# bmsSlave_balancing.net
KiCad netlist of a schematic drawn in Altium Designer
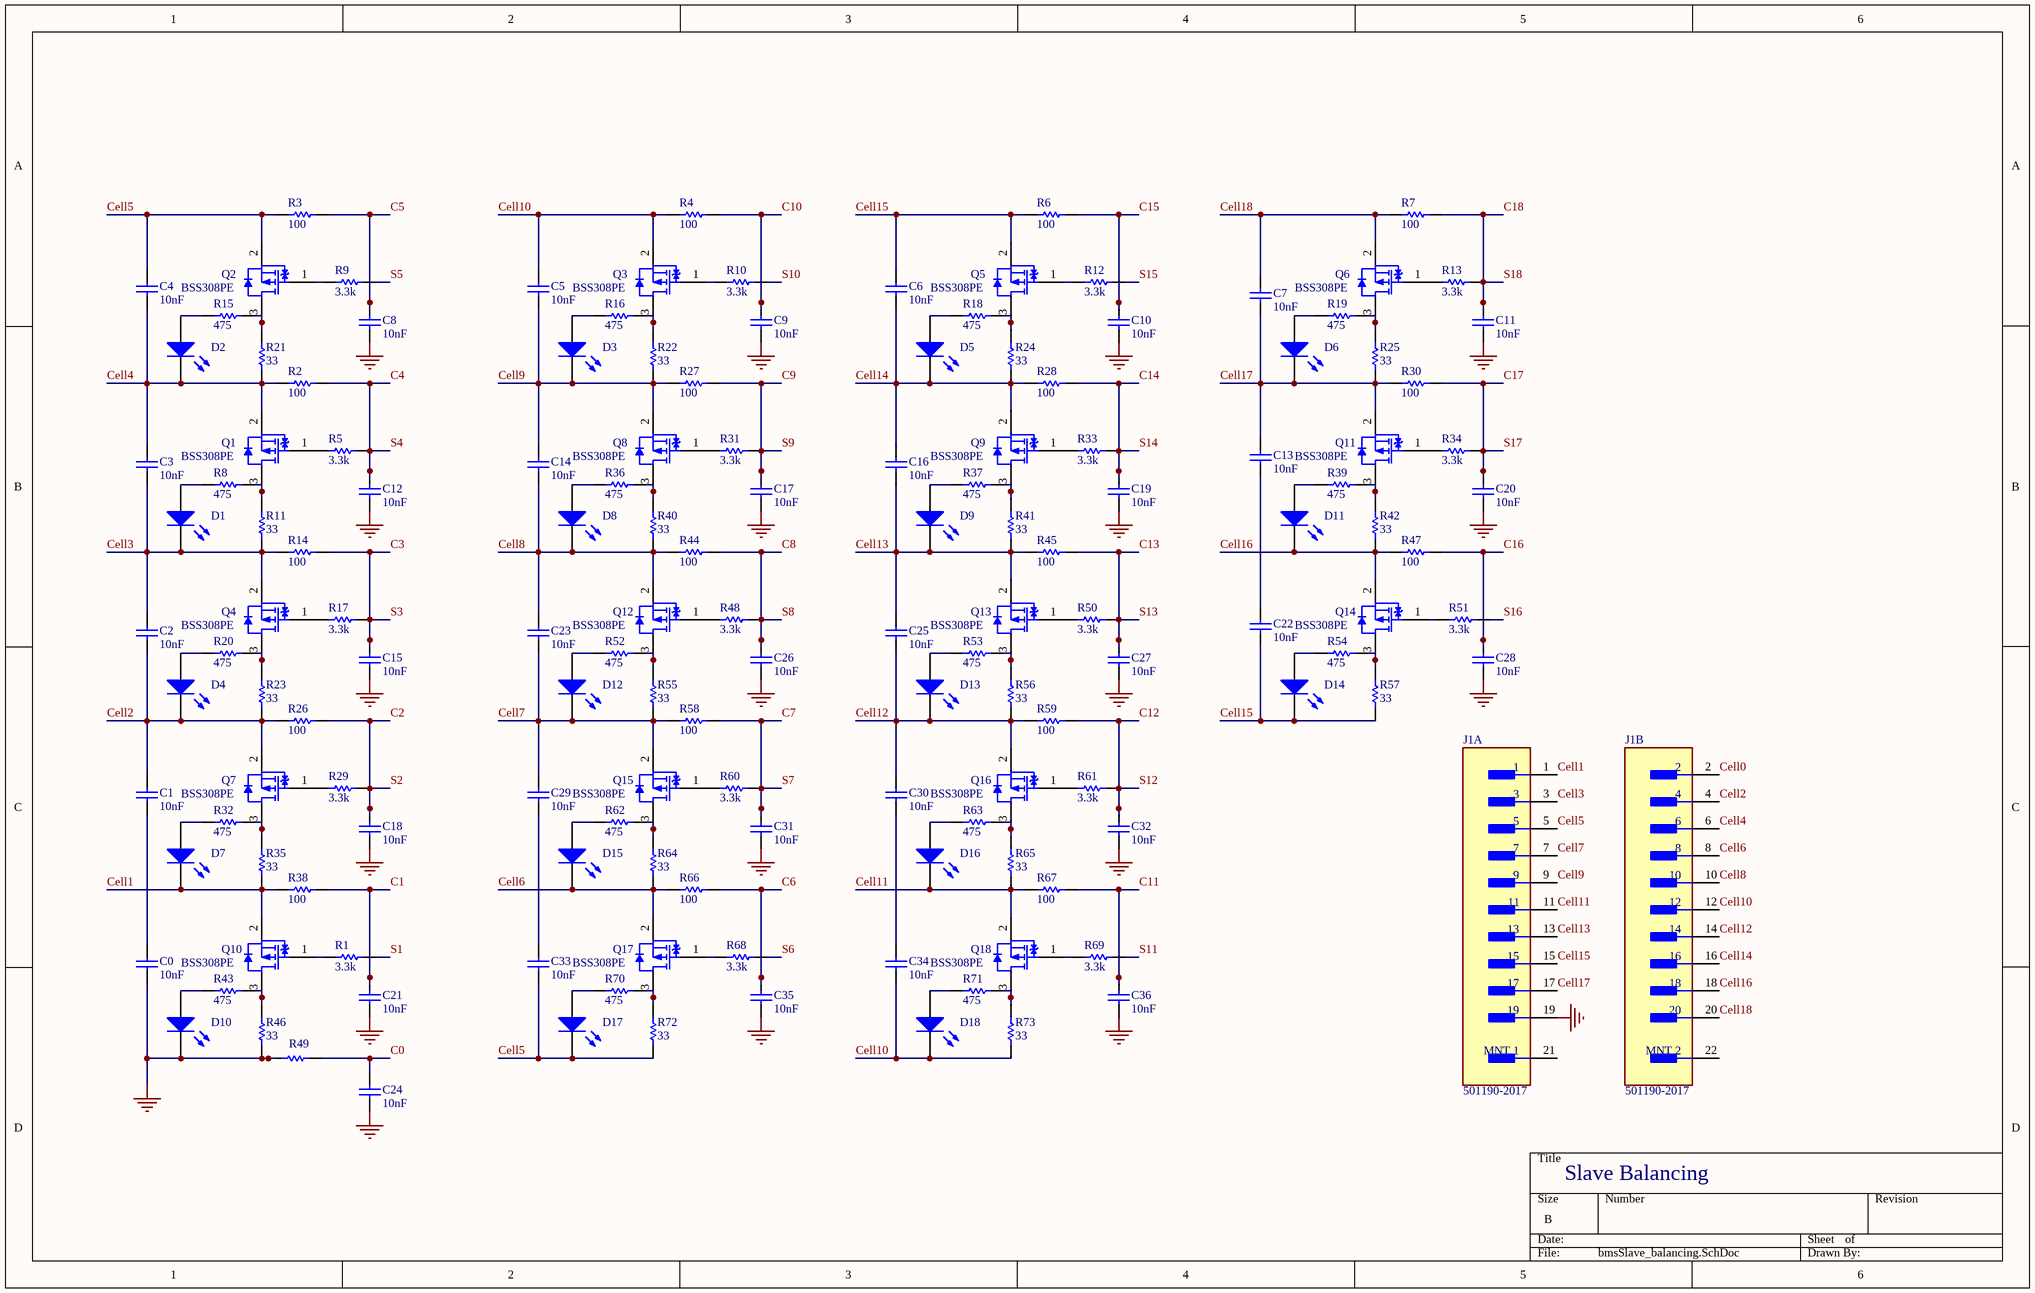
[diagram p0: bmsSlave_balancing.SchDoc]

(export (version "E")
  (design (tool "Eeschema 10.0.6"))
  (components
    (comp (ref "C0")
      (value "10nF")
      (description "Capacitor")
      (libsource (lib "Simulation Generic Components") (part "Capacitor"))
    )
    (comp (ref "C1")
      (value "10nF")
      (description "Capacitor")
      (libsource (lib "Simulation Generic Components") (part "Capacitor"))
    )
    (comp (ref "C2")
      (value "10nF")
      (description "Capacitor")
      (libsource (lib "Simulation Generic Components") (part "Capacitor"))
    )
    (comp (ref "C3")
      (value "10nF")
      (description "Capacitor")
      (libsource (lib "Simulation Generic Components") (part "Capacitor"))
    )
    (comp (ref "C4")
      (value "10nF")
      (description "Capacitor")
      (libsource (lib "Simulation Generic Components") (part "Capacitor"))
    )
    (comp (ref "C5")
      (value "10nF")
      (description "Capacitor")
      (libsource (lib "Simulation Generic Components") (part "Capacitor"))
    )
    (comp (ref "C6")
      (value "10nF")
      (description "Capacitor")
      (libsource (lib "Simulation Generic Components") (part "Capacitor"))
    )
    (comp (ref "C7")
      (value "10nF")
      (description "Capacitor")
      (libsource (lib "Simulation Generic Components") (part "Capacitor"))
    )
    (comp (ref "C8")
      (value "10nF")
      (description "Capacitor")
      (libsource (lib "Simulation Generic Components") (part "Capacitor"))
    )
    (comp (ref "C9")
      (value "10nF")
      (description "Capacitor")
      (libsource (lib "Simulation Generic Components") (part "Capacitor"))
    )
    (comp (ref "C10")
      (value "10nF")
      (description "Capacitor")
      (libsource (lib "Simulation Generic Components") (part "Capacitor"))
    )
    (comp (ref "C11")
      (value "10nF")
      (description "Capacitor")
      (libsource (lib "Simulation Generic Components") (part "Capacitor"))
    )
    (comp (ref "C12")
      (value "10nF")
      (description "Capacitor")
      (libsource (lib "Simulation Generic Components") (part "Capacitor"))
    )
    (comp (ref "C13")
      (value "10nF")
      (description "Capacitor")
      (libsource (lib "Simulation Generic Components") (part "Capacitor"))
    )
    (comp (ref "C14")
      (value "10nF")
      (description "Capacitor")
      (libsource (lib "Simulation Generic Components") (part "Capacitor"))
    )
    (comp (ref "C15")
      (value "10nF")
      (description "Capacitor")
      (libsource (lib "Simulation Generic Components") (part "Capacitor"))
    )
    (comp (ref "C16")
      (value "10nF")
      (description "Capacitor")
      (libsource (lib "Simulation Generic Components") (part "Capacitor"))
    )
    (comp (ref "C17")
      (value "10nF")
      (description "Capacitor")
      (libsource (lib "Simulation Generic Components") (part "Capacitor"))
    )
    (comp (ref "C18")
      (value "10nF")
      (description "Capacitor")
      (libsource (lib "Simulation Generic Components") (part "Capacitor"))
    )
    (comp (ref "C19")
      (value "10nF")
      (description "Capacitor")
      (libsource (lib "Simulation Generic Components") (part "Capacitor"))
    )
    (comp (ref "C20")
      (value "10nF")
      (description "Capacitor")
      (libsource (lib "Simulation Generic Components") (part "Capacitor"))
    )
    (comp (ref "C21")
      (value "10nF")
      (description "Capacitor")
      (libsource (lib "Simulation Generic Components") (part "Capacitor"))
    )
    (comp (ref "C22")
      (value "10nF")
      (description "Capacitor")
      (libsource (lib "Simulation Generic Components") (part "Capacitor"))
    )
    (comp (ref "C23")
      (value "10nF")
      (description "Capacitor")
      (libsource (lib "Simulation Generic Components") (part "Capacitor"))
    )
    (comp (ref "C24")
      (value "10nF")
      (description "Capacitor")
      (libsource (lib "Simulation Generic Components") (part "Capacitor"))
    )
    (comp (ref "C25")
      (value "10nF")
      (description "Capacitor")
      (libsource (lib "Simulation Generic Components") (part "Capacitor"))
    )
    (comp (ref "C26")
      (value "10nF")
      (description "Capacitor")
      (libsource (lib "Simulation Generic Components") (part "Capacitor"))
    )
    (comp (ref "C27")
      (value "10nF")
      (description "Capacitor")
      (libsource (lib "Simulation Generic Components") (part "Capacitor"))
    )
    (comp (ref "C28")
      (value "10nF")
      (description "Capacitor")
      (libsource (lib "Simulation Generic Components") (part "Capacitor"))
    )
    (comp (ref "C29")
      (value "10nF")
      (description "Capacitor")
      (libsource (lib "Simulation Generic Components") (part "Capacitor"))
    )
    (comp (ref "C30")
      (value "10nF")
      (description "Capacitor")
      (libsource (lib "Simulation Generic Components") (part "Capacitor"))
    )
    (comp (ref "C31")
      (value "10nF")
      (description "Capacitor")
      (libsource (lib "Simulation Generic Components") (part "Capacitor"))
    )
    (comp (ref "C32")
      (value "10nF")
      (description "Capacitor")
      (libsource (lib "Simulation Generic Components") (part "Capacitor"))
    )
    (comp (ref "C33")
      (value "10nF")
      (description "Capacitor")
      (libsource (lib "Simulation Generic Components") (part "Capacitor"))
    )
    (comp (ref "C34")
      (value "10nF")
      (description "Capacitor")
      (libsource (lib "Simulation Generic Components") (part "Capacitor"))
    )
    (comp (ref "C35")
      (value "10nF")
      (description "Capacitor")
      (libsource (lib "Simulation Generic Components") (part "Capacitor"))
    )
    (comp (ref "C36")
      (value "10nF")
      (description "Capacitor")
      (libsource (lib "Simulation Generic Components") (part "Capacitor"))
    )
    (comp (ref "D1")
      (value "Light-Emitting Diode")
      (libsource (lib "Simulation Generic Components") (part "LED"))
    )
    (comp (ref "D2")
      (value "Light-Emitting Diode")
      (libsource (lib "Simulation Generic Components") (part "LED"))
    )
    (comp (ref "D3")
      (value "Light-Emitting Diode")
      (libsource (lib "Simulation Generic Components") (part "LED"))
    )
    (comp (ref "D4")
      (value "Light-Emitting Diode")
      (libsource (lib "Simulation Generic Components") (part "LED"))
    )
    (comp (ref "D5")
      (value "Light-Emitting Diode")
      (libsource (lib "Simulation Generic Components") (part "LED"))
    )
    (comp (ref "D6")
      (value "Light-Emitting Diode")
      (libsource (lib "Simulation Generic Components") (part "LED"))
    )
    (comp (ref "D7")
      (value "Light-Emitting Diode")
      (libsource (lib "Simulation Generic Components") (part "LED"))
    )
    (comp (ref "D8")
      (value "Light-Emitting Diode")
      (libsource (lib "Simulation Generic Components") (part "LED"))
    )
    (comp (ref "D9")
      (value "Light-Emitting Diode")
      (libsource (lib "Simulation Generic Components") (part "LED"))
    )
    (comp (ref "D10")
      (value "Light-Emitting Diode")
      (libsource (lib "Simulation Generic Components") (part "LED"))
    )
    (comp (ref "D11")
      (value "Light-Emitting Diode")
      (libsource (lib "Simulation Generic Components") (part "LED"))
    )
    (comp (ref "D12")
      (value "Light-Emitting Diode")
      (libsource (lib "Simulation Generic Components") (part "LED"))
    )
    (comp (ref "D13")
      (value "Light-Emitting Diode")
      (libsource (lib "Simulation Generic Components") (part "LED"))
    )
    (comp (ref "D14")
      (value "Light-Emitting Diode")
      (libsource (lib "Simulation Generic Components") (part "LED"))
    )
    (comp (ref "D15")
      (value "Light-Emitting Diode")
      (libsource (lib "Simulation Generic Components") (part "LED"))
    )
    (comp (ref "D16")
      (value "Light-Emitting Diode")
      (libsource (lib "Simulation Generic Components") (part "LED"))
    )
    (comp (ref "D17")
      (value "Light-Emitting Diode")
      (libsource (lib "Simulation Generic Components") (part "LED"))
    )
    (comp (ref "D18")
      (value "Light-Emitting Diode")
      (libsource (lib "Simulation Generic Components") (part "LED"))
    )
    (comp (ref "J1")
      (value "501190-2017")
      (footprint "FP-501190-2017-MFG")
      (description "CONN HEADER SMD 20POS 1MM")
      (libsource (lib "Altium Content Vault") (part "3088fde206a7053fe950ea66454f304"))
    )
    (comp (ref "Q1")
      (value "BSS308PE")
      (footprint "INF-PG-SOT23_L")
      (fields (field (name "MANUFACTURER") "Infineon"))
      (libsource (lib "Altium Content Vault") (part "INF-BSS3XXPE-PG-SOT23-3"))
    )
    (comp (ref "Q2")
      (value "BSS308PE")
      (footprint "INF-PG-SOT23_L")
      (fields (field (name "MANUFACTURER") "Infineon"))
      (libsource (lib "Altium Content Vault") (part "INF-BSS3XXPE-PG-SOT23-3"))
    )
    (comp (ref "Q3")
      (value "BSS308PE")
      (footprint "INF-PG-SOT23_L")
      (fields (field (name "MANUFACTURER") "Infineon"))
      (libsource (lib "Altium Content Vault") (part "INF-BSS3XXPE-PG-SOT23-3"))
    )
    (comp (ref "Q4")
      (value "BSS308PE")
      (footprint "INF-PG-SOT23_L")
      (fields (field (name "MANUFACTURER") "Infineon"))
      (libsource (lib "Altium Content Vault") (part "INF-BSS3XXPE-PG-SOT23-3"))
    )
    (comp (ref "Q5")
      (value "BSS308PE")
      (footprint "INF-PG-SOT23_L")
      (fields (field (name "MANUFACTURER") "Infineon"))
      (libsource (lib "Altium Content Vault") (part "INF-BSS3XXPE-PG-SOT23-3"))
    )
    (comp (ref "Q6")
      (value "BSS308PE")
      (footprint "INF-PG-SOT23_L")
      (fields (field (name "MANUFACTURER") "Infineon"))
      (libsource (lib "Altium Content Vault") (part "INF-BSS3XXPE-PG-SOT23-3"))
    )
    (comp (ref "Q7")
      (value "BSS308PE")
      (footprint "INF-PG-SOT23_L")
      (fields (field (name "MANUFACTURER") "Infineon"))
      (libsource (lib "Altium Content Vault") (part "INF-BSS3XXPE-PG-SOT23-3"))
    )
    (comp (ref "Q8")
      (value "BSS308PE")
      (footprint "INF-PG-SOT23_L")
      (fields (field (name "MANUFACTURER") "Infineon"))
      (libsource (lib "Altium Content Vault") (part "INF-BSS3XXPE-PG-SOT23-3"))
    )
    (comp (ref "Q9")
      (value "BSS308PE")
      (footprint "INF-PG-SOT23_L")
      (fields (field (name "MANUFACTURER") "Infineon"))
      (libsource (lib "Altium Content Vault") (part "INF-BSS3XXPE-PG-SOT23-3"))
    )
    (comp (ref "Q10")
      (value "BSS308PE")
      (footprint "INF-PG-SOT23_L")
      (fields (field (name "MANUFACTURER") "Infineon"))
      (libsource (lib "Altium Content Vault") (part "INF-BSS3XXPE-PG-SOT23-3"))
    )
    (comp (ref "Q11")
      (value "BSS308PE")
      (footprint "INF-PG-SOT23_L")
      (fields (field (name "MANUFACTURER") "Infineon"))
      (libsource (lib "Altium Content Vault") (part "INF-BSS3XXPE-PG-SOT23-3"))
    )
    (comp (ref "Q12")
      (value "BSS308PE")
      (footprint "INF-PG-SOT23_L")
      (fields (field (name "MANUFACTURER") "Infineon"))
      (libsource (lib "Altium Content Vault") (part "INF-BSS3XXPE-PG-SOT23-3"))
    )
    (comp (ref "Q13")
      (value "BSS308PE")
      (footprint "INF-PG-SOT23_L")
      (fields (field (name "MANUFACTURER") "Infineon"))
      (libsource (lib "Altium Content Vault") (part "INF-BSS3XXPE-PG-SOT23-3"))
    )
    (comp (ref "Q14")
      (value "BSS308PE")
      (footprint "INF-PG-SOT23_L")
      (fields (field (name "MANUFACTURER") "Infineon"))
      (libsource (lib "Altium Content Vault") (part "INF-BSS3XXPE-PG-SOT23-3"))
    )
    (comp (ref "Q15")
      (value "BSS308PE")
      (footprint "INF-PG-SOT23_L")
      (fields (field (name "MANUFACTURER") "Infineon"))
      (libsource (lib "Altium Content Vault") (part "INF-BSS3XXPE-PG-SOT23-3"))
    )
    (comp (ref "Q16")
      (value "BSS308PE")
      (footprint "INF-PG-SOT23_L")
      (fields (field (name "MANUFACTURER") "Infineon"))
      (libsource (lib "Altium Content Vault") (part "INF-BSS3XXPE-PG-SOT23-3"))
    )
    (comp (ref "Q17")
      (value "BSS308PE")
      (footprint "INF-PG-SOT23_L")
      (fields (field (name "MANUFACTURER") "Infineon"))
      (libsource (lib "Altium Content Vault") (part "INF-BSS3XXPE-PG-SOT23-3"))
    )
    (comp (ref "Q18")
      (value "BSS308PE")
      (footprint "INF-PG-SOT23_L")
      (fields (field (name "MANUFACTURER") "Infineon"))
      (libsource (lib "Altium Content Vault") (part "INF-BSS3XXPE-PG-SOT23-3"))
    )
    (comp (ref "R1")
      (value "3.3k")
      (description "Resistor")
      (libsource (lib "Simulation Generic Components") (part "Resistor"))
    )
    (comp (ref "R2")
      (value "100")
      (description "Resistor")
      (libsource (lib "Simulation Generic Components") (part "Resistor"))
    )
    (comp (ref "R3")
      (value "100")
      (description "Resistor")
      (libsource (lib "Simulation Generic Components") (part "Resistor"))
    )
    (comp (ref "R4")
      (value "100")
      (description "Resistor")
      (libsource (lib "Simulation Generic Components") (part "Resistor"))
    )
    (comp (ref "R5")
      (value "3.3k")
      (description "Resistor")
      (libsource (lib "Simulation Generic Components") (part "Resistor"))
    )
    (comp (ref "R6")
      (value "100")
      (description "Resistor")
      (libsource (lib "Simulation Generic Components") (part "Resistor"))
    )
    (comp (ref "R7")
      (value "100")
      (description "Resistor")
      (libsource (lib "Simulation Generic Components") (part "Resistor"))
    )
    (comp (ref "R8")
      (value "475")
      (description "Resistor")
      (libsource (lib "Simulation Generic Components") (part "Resistor"))
    )
    (comp (ref "R9")
      (value "3.3k")
      (description "Resistor")
      (libsource (lib "Simulation Generic Components") (part "Resistor"))
    )
    (comp (ref "R10")
      (value "3.3k")
      (description "Resistor")
      (libsource (lib "Simulation Generic Components") (part "Resistor"))
    )
    (comp (ref "R11")
      (value "33")
      (description "Resistor")
      (libsource (lib "Simulation Generic Components") (part "Resistor"))
    )
    (comp (ref "R12")
      (value "3.3k")
      (description "Resistor")
      (libsource (lib "Simulation Generic Components") (part "Resistor"))
    )
    (comp (ref "R13")
      (value "3.3k")
      (description "Resistor")
      (libsource (lib "Simulation Generic Components") (part "Resistor"))
    )
    (comp (ref "R14")
      (value "100")
      (description "Resistor")
      (libsource (lib "Simulation Generic Components") (part "Resistor"))
    )
    (comp (ref "R15")
      (value "475")
      (description "Resistor")
      (libsource (lib "Simulation Generic Components") (part "Resistor"))
    )
    (comp (ref "R16")
      (value "475")
      (description "Resistor")
      (libsource (lib "Simulation Generic Components") (part "Resistor"))
    )
    (comp (ref "R17")
      (value "3.3k")
      (description "Resistor")
      (libsource (lib "Simulation Generic Components") (part "Resistor"))
    )
    (comp (ref "R18")
      (value "475")
      (description "Resistor")
      (libsource (lib "Simulation Generic Components") (part "Resistor"))
    )
    (comp (ref "R19")
      (value "475")
      (description "Resistor")
      (libsource (lib "Simulation Generic Components") (part "Resistor"))
    )
    (comp (ref "R20")
      (value "475")
      (description "Resistor")
      (libsource (lib "Simulation Generic Components") (part "Resistor"))
    )
    (comp (ref "R21")
      (value "33")
      (description "Resistor")
      (libsource (lib "Simulation Generic Components") (part "Resistor"))
    )
    (comp (ref "R22")
      (value "33")
      (description "Resistor")
      (libsource (lib "Simulation Generic Components") (part "Resistor"))
    )
    (comp (ref "R23")
      (value "33")
      (description "Resistor")
      (libsource (lib "Simulation Generic Components") (part "Resistor"))
    )
    (comp (ref "R24")
      (value "33")
      (description "Resistor")
      (libsource (lib "Simulation Generic Components") (part "Resistor"))
    )
    (comp (ref "R25")
      (value "33")
      (description "Resistor")
      (libsource (lib "Simulation Generic Components") (part "Resistor"))
    )
    (comp (ref "R26")
      (value "100")
      (description "Resistor")
      (libsource (lib "Simulation Generic Components") (part "Resistor"))
    )
    (comp (ref "R27")
      (value "100")
      (description "Resistor")
      (libsource (lib "Simulation Generic Components") (part "Resistor"))
    )
    (comp (ref "R28")
      (value "100")
      (description "Resistor")
      (libsource (lib "Simulation Generic Components") (part "Resistor"))
    )
    (comp (ref "R29")
      (value "3.3k")
      (description "Resistor")
      (libsource (lib "Simulation Generic Components") (part "Resistor"))
    )
    (comp (ref "R30")
      (value "100")
      (description "Resistor")
      (libsource (lib "Simulation Generic Components") (part "Resistor"))
    )
    (comp (ref "R31")
      (value "3.3k")
      (description "Resistor")
      (libsource (lib "Simulation Generic Components") (part "Resistor"))
    )
    (comp (ref "R32")
      (value "475")
      (description "Resistor")
      (libsource (lib "Simulation Generic Components") (part "Resistor"))
    )
    (comp (ref "R33")
      (value "3.3k")
      (description "Resistor")
      (libsource (lib "Simulation Generic Components") (part "Resistor"))
    )
    (comp (ref "R34")
      (value "3.3k")
      (description "Resistor")
      (libsource (lib "Simulation Generic Components") (part "Resistor"))
    )
    (comp (ref "R35")
      (value "33")
      (description "Resistor")
      (libsource (lib "Simulation Generic Components") (part "Resistor"))
    )
    (comp (ref "R36")
      (value "475")
      (description "Resistor")
      (libsource (lib "Simulation Generic Components") (part "Resistor"))
    )
    (comp (ref "R37")
      (value "475")
      (description "Resistor")
      (libsource (lib "Simulation Generic Components") (part "Resistor"))
    )
    (comp (ref "R38")
      (value "100")
      (description "Resistor")
      (libsource (lib "Simulation Generic Components") (part "Resistor"))
    )
    (comp (ref "R39")
      (value "475")
      (description "Resistor")
      (libsource (lib "Simulation Generic Components") (part "Resistor"))
    )
    (comp (ref "R40")
      (value "33")
      (description "Resistor")
      (libsource (lib "Simulation Generic Components") (part "Resistor"))
    )
    (comp (ref "R41")
      (value "33")
      (description "Resistor")
      (libsource (lib "Simulation Generic Components") (part "Resistor"))
    )
    (comp (ref "R42")
      (value "33")
      (description "Resistor")
      (libsource (lib "Simulation Generic Components") (part "Resistor"))
    )
    (comp (ref "R43")
      (value "475")
      (description "Resistor")
      (libsource (lib "Simulation Generic Components") (part "Resistor"))
    )
    (comp (ref "R44")
      (value "100")
      (description "Resistor")
      (libsource (lib "Simulation Generic Components") (part "Resistor"))
    )
    (comp (ref "R45")
      (value "100")
      (description "Resistor")
      (libsource (lib "Simulation Generic Components") (part "Resistor"))
    )
    (comp (ref "R46")
      (value "33")
      (description "Resistor")
      (libsource (lib "Simulation Generic Components") (part "Resistor"))
    )
    (comp (ref "R47")
      (value "100")
      (description "Resistor")
      (libsource (lib "Simulation Generic Components") (part "Resistor"))
    )
    (comp (ref "R48")
      (value "3.3k")
      (description "Resistor")
      (libsource (lib "Simulation Generic Components") (part "Resistor"))
    )
    (comp (ref "R49") (value "Resistor") (libsource (lib "Simulation Generic Components") (part "Resistor")))
    (comp (ref "R50")
      (value "3.3k")
      (description "Resistor")
      (libsource (lib "Simulation Generic Components") (part "Resistor"))
    )
    (comp (ref "R51")
      (value "3.3k")
      (description "Resistor")
      (libsource (lib "Simulation Generic Components") (part "Resistor"))
    )
    (comp (ref "R52")
      (value "475")
      (description "Resistor")
      (libsource (lib "Simulation Generic Components") (part "Resistor"))
    )
    (comp (ref "R53")
      (value "475")
      (description "Resistor")
      (libsource (lib "Simulation Generic Components") (part "Resistor"))
    )
    (comp (ref "R54")
      (value "475")
      (description "Resistor")
      (libsource (lib "Simulation Generic Components") (part "Resistor"))
    )
    (comp (ref "R55")
      (value "33")
      (description "Resistor")
      (libsource (lib "Simulation Generic Components") (part "Resistor"))
    )
    (comp (ref "R56")
      (value "33")
      (description "Resistor")
      (libsource (lib "Simulation Generic Components") (part "Resistor"))
    )
    (comp (ref "R57")
      (value "33")
      (description "Resistor")
      (libsource (lib "Simulation Generic Components") (part "Resistor"))
    )
    (comp (ref "R58")
      (value "100")
      (description "Resistor")
      (libsource (lib "Simulation Generic Components") (part "Resistor"))
    )
    (comp (ref "R59")
      (value "100")
      (description "Resistor")
      (libsource (lib "Simulation Generic Components") (part "Resistor"))
    )
    (comp (ref "R60")
      (value "3.3k")
      (description "Resistor")
      (libsource (lib "Simulation Generic Components") (part "Resistor"))
    )
    (comp (ref "R61")
      (value "3.3k")
      (description "Resistor")
      (libsource (lib "Simulation Generic Components") (part "Resistor"))
    )
    (comp (ref "R62")
      (value "475")
      (description "Resistor")
      (libsource (lib "Simulation Generic Components") (part "Resistor"))
    )
    (comp (ref "R63")
      (value "475")
      (description "Resistor")
      (libsource (lib "Simulation Generic Components") (part "Resistor"))
    )
    (comp (ref "R64")
      (value "33")
      (description "Resistor")
      (libsource (lib "Simulation Generic Components") (part "Resistor"))
    )
    (comp (ref "R65")
      (value "33")
      (description "Resistor")
      (libsource (lib "Simulation Generic Components") (part "Resistor"))
    )
    (comp (ref "R66")
      (value "100")
      (description "Resistor")
      (libsource (lib "Simulation Generic Components") (part "Resistor"))
    )
    (comp (ref "R67")
      (value "100")
      (description "Resistor")
      (libsource (lib "Simulation Generic Components") (part "Resistor"))
    )
    (comp (ref "R68")
      (value "3.3k")
      (description "Resistor")
      (libsource (lib "Simulation Generic Components") (part "Resistor"))
    )
    (comp (ref "R69")
      (value "3.3k")
      (description "Resistor")
      (libsource (lib "Simulation Generic Components") (part "Resistor"))
    )
    (comp (ref "R70")
      (value "475")
      (description "Resistor")
      (libsource (lib "Simulation Generic Components") (part "Resistor"))
    )
    (comp (ref "R71")
      (value "475")
      (description "Resistor")
      (libsource (lib "Simulation Generic Components") (part "Resistor"))
    )
    (comp (ref "R72")
      (value "33")
      (description "Resistor")
      (libsource (lib "Simulation Generic Components") (part "Resistor"))
    )
    (comp (ref "R73")
      (value "33")
      (description "Resistor")
      (libsource (lib "Simulation Generic Components") (part "Resistor"))
    )
  )
  (nets
    (net (code "1") (name "/C0") (class "Default")
      (node (ref "C24") (pin "2") (pinfunction "2_2") (pintype "passive"))
      (node (ref "R49") (pin "1") (pinfunction "1_1") (pintype "passive"))
    )
    (net (code "2") (name "/C1") (class "Default")
      (node (ref "C21") (pin "2") (pinfunction "2_2") (pintype "passive"))
      (node (ref "R38") (pin "1") (pinfunction "1_1") (pintype "passive"))
    )
    (net (code "3") (name "/C2") (class "Default")
      (node (ref "C18") (pin "2") (pinfunction "2_2") (pintype "passive"))
      (node (ref "R26") (pin "1") (pinfunction "1_1") (pintype "passive"))
      (node (ref "R29") (pin "1") (pinfunction "1_1") (pintype "passive"))
    )
    (net (code "4") (name "/C3") (class "Default")
      (node (ref "C15") (pin "2") (pinfunction "2_2") (pintype "passive"))
      (node (ref "R14") (pin "1") (pinfunction "1_1") (pintype "passive"))
      (node (ref "R17") (pin "1") (pinfunction "1_1") (pintype "passive"))
    )
    (net (code "5") (name "/C4") (class "Default")
      (node (ref "C12") (pin "2") (pinfunction "2_2") (pintype "passive"))
      (node (ref "R2") (pin "1") (pinfunction "1_1") (pintype "passive"))
      (node (ref "R5") (pin "1") (pinfunction "1_1") (pintype "passive"))
    )
    (net (code "6") (name "/C5") (class "Default")
      (node (ref "C8") (pin "2") (pinfunction "2_2") (pintype "passive"))
      (node (ref "R3") (pin "1") (pinfunction "1_1") (pintype "passive"))
    )
    (net (code "7") (name "/C6") (class "Default")
      (node (ref "C35") (pin "2") (pinfunction "2_2") (pintype "passive"))
      (node (ref "R66") (pin "1") (pinfunction "1_1") (pintype "passive"))
    )
    (net (code "8") (name "/C7") (class "Default")
      (node (ref "C31") (pin "2") (pinfunction "2_2") (pintype "passive"))
      (node (ref "R58") (pin "1") (pinfunction "1_1") (pintype "passive"))
      (node (ref "R60") (pin "1") (pinfunction "1_1") (pintype "passive"))
    )
    (net (code "9") (name "/C8") (class "Default")
      (node (ref "C26") (pin "2") (pinfunction "2_2") (pintype "passive"))
      (node (ref "R44") (pin "1") (pinfunction "1_1") (pintype "passive"))
      (node (ref "R48") (pin "1") (pinfunction "1_1") (pintype "passive"))
    )
    (net (code "10") (name "/C9") (class "Default")
      (node (ref "C17") (pin "2") (pinfunction "2_2") (pintype "passive"))
      (node (ref "R27") (pin "1") (pinfunction "1_1") (pintype "passive"))
      (node (ref "R31") (pin "1") (pinfunction "1_1") (pintype "passive"))
    )
    (net (code "11") (name "/C10") (class "Default")
      (node (ref "C9") (pin "2") (pinfunction "2_2") (pintype "passive"))
      (node (ref "R4") (pin "1") (pinfunction "1_1") (pintype "passive"))
    )
    (net (code "12") (name "/C11") (class "Default")
      (node (ref "C36") (pin "2") (pinfunction "2_2") (pintype "passive"))
      (node (ref "R67") (pin "1") (pinfunction "1_1") (pintype "passive"))
    )
    (net (code "13") (name "/C12") (class "Default")
      (node (ref "C32") (pin "2") (pinfunction "2_2") (pintype "passive"))
      (node (ref "R59") (pin "1") (pinfunction "1_1") (pintype "passive"))
      (node (ref "R61") (pin "1") (pinfunction "1_1") (pintype "passive"))
    )
    (net (code "14") (name "/C13") (class "Default")
      (node (ref "C27") (pin "2") (pinfunction "2_2") (pintype "passive"))
      (node (ref "R45") (pin "1") (pinfunction "1_1") (pintype "passive"))
      (node (ref "R50") (pin "1") (pinfunction "1_1") (pintype "passive"))
    )
    (net (code "15") (name "/C14") (class "Default")
      (node (ref "C19") (pin "2") (pinfunction "2_2") (pintype "passive"))
      (node (ref "R28") (pin "1") (pinfunction "1_1") (pintype "passive"))
      (node (ref "R33") (pin "1") (pinfunction "1_1") (pintype "passive"))
    )
    (net (code "16") (name "/C15") (class "Default")
      (node (ref "C10") (pin "2") (pinfunction "2_2") (pintype "passive"))
      (node (ref "R6") (pin "1") (pinfunction "1_1") (pintype "passive"))
    )
    (net (code "17") (name "/C16") (class "Default")
      (node (ref "C28") (pin "2") (pinfunction "2_2") (pintype "passive"))
      (node (ref "R47") (pin "1") (pinfunction "1_1") (pintype "passive"))
    )
    (net (code "18") (name "/C17") (class "Default")
      (node (ref "C20") (pin "2") (pinfunction "2_2") (pintype "passive"))
      (node (ref "R30") (pin "1") (pinfunction "1_1") (pintype "passive"))
      (node (ref "R34") (pin "1") (pinfunction "1_1") (pintype "passive"))
    )
    (net (code "19") (name "/C18") (class "Default")
      (node (ref "C11") (pin "2") (pinfunction "2_2") (pintype "passive"))
      (node (ref "R13") (pin "1") (pinfunction "1_1") (pintype "passive"))
      (node (ref "R7") (pin "1") (pinfunction "1_1") (pintype "passive"))
    )
    (net (code "20") (name "/Cell0") (class "Default")
      (node (ref "J1") (pin "2") (pinfunction "2_2") (pintype "passive"))
    )
    (net (code "21") (name "/Cell1") (class "Default")
      (node (ref "D7") (pin "2") (pinfunction "K_2") (pintype "passive"))
      (node (ref "J1") (pin "1") (pinfunction "1_1") (pintype "passive"))
      (node (ref "Q10") (pin "2") (pinfunction "SOURCE_2") (pintype "passive"))
      (node (ref "R35") (pin "2") (pinfunction "2_2") (pintype "passive"))
      (node (ref "R38") (pin "2") (pinfunction "2_2") (pintype "passive"))
    )
    (net (code "22") (name "/Cell2") (class "Default")
      (node (ref "C1") (pin "2") (pinfunction "2_2") (pintype "passive"))
      (node (ref "C2") (pin "1") (pinfunction "1_1") (pintype "passive"))
      (node (ref "D4") (pin "2") (pinfunction "K_2") (pintype "passive"))
      (node (ref "J1") (pin "4") (pinfunction "4_4") (pintype "passive"))
      (node (ref "Q7") (pin "2") (pinfunction "SOURCE_2") (pintype "passive"))
      (node (ref "R23") (pin "2") (pinfunction "2_2") (pintype "passive"))
      (node (ref "R26") (pin "2") (pinfunction "2_2") (pintype "passive"))
    )
    (net (code "23") (name "/Cell3") (class "Default")
      (node (ref "C2") (pin "2") (pinfunction "2_2") (pintype "passive"))
      (node (ref "C3") (pin "1") (pinfunction "1_1") (pintype "passive"))
      (node (ref "D1") (pin "2") (pinfunction "K_2") (pintype "passive"))
      (node (ref "J1") (pin "3") (pinfunction "3_3") (pintype "passive"))
      (node (ref "Q4") (pin "2") (pinfunction "SOURCE_2") (pintype "passive"))
      (node (ref "R11") (pin "2") (pinfunction "2_2") (pintype "passive"))
      (node (ref "R14") (pin "2") (pinfunction "2_2") (pintype "passive"))
    )
    (net (code "24") (name "/Cell4") (class "Default")
      (node (ref "C3") (pin "2") (pinfunction "2_2") (pintype "passive"))
      (node (ref "C4") (pin "1") (pinfunction "1_1") (pintype "passive"))
      (node (ref "D2") (pin "2") (pinfunction "K_2") (pintype "passive"))
      (node (ref "J1") (pin "6") (pinfunction "6_6") (pintype "passive"))
      (node (ref "Q1") (pin "2") (pinfunction "SOURCE_2") (pintype "passive"))
      (node (ref "R2") (pin "2") (pinfunction "2_2") (pintype "passive"))
      (node (ref "R21") (pin "2") (pinfunction "2_2") (pintype "passive"))
    )
    (net (code "25") (name "/Cell5") (class "Default")
      (node (ref "C33") (pin "1") (pinfunction "1_1") (pintype "passive"))
      (node (ref "C4") (pin "2") (pinfunction "2_2") (pintype "passive"))
      (node (ref "D17") (pin "2") (pinfunction "K_2") (pintype "passive"))
      (node (ref "J1") (pin "5") (pinfunction "5_5") (pintype "passive"))
      (node (ref "Q2") (pin "2") (pinfunction "SOURCE_2") (pintype "passive"))
      (node (ref "R3") (pin "2") (pinfunction "2_2") (pintype "passive"))
      (node (ref "R72") (pin "2") (pinfunction "2_2") (pintype "passive"))
    )
    (net (code "26") (name "/Cell6") (class "Default")
      (node (ref "D15") (pin "2") (pinfunction "K_2") (pintype "passive"))
      (node (ref "J1") (pin "8") (pinfunction "8_8") (pintype "passive"))
      (node (ref "Q17") (pin "2") (pinfunction "SOURCE_2") (pintype "passive"))
      (node (ref "R64") (pin "2") (pinfunction "2_2") (pintype "passive"))
      (node (ref "R66") (pin "2") (pinfunction "2_2") (pintype "passive"))
    )
    (net (code "27") (name "/Cell7") (class "Default")
      (node (ref "C23") (pin "1") (pinfunction "1_1") (pintype "passive"))
      (node (ref "C29") (pin "2") (pinfunction "2_2") (pintype "passive"))
      (node (ref "D12") (pin "2") (pinfunction "K_2") (pintype "passive"))
      (node (ref "J1") (pin "7") (pinfunction "7_7") (pintype "passive"))
      (node (ref "Q15") (pin "2") (pinfunction "SOURCE_2") (pintype "passive"))
      (node (ref "R55") (pin "2") (pinfunction "2_2") (pintype "passive"))
      (node (ref "R58") (pin "2") (pinfunction "2_2") (pintype "passive"))
    )
    (net (code "28") (name "/Cell8") (class "Default")
      (node (ref "C14") (pin "1") (pinfunction "1_1") (pintype "passive"))
      (node (ref "C23") (pin "2") (pinfunction "2_2") (pintype "passive"))
      (node (ref "D8") (pin "2") (pinfunction "K_2") (pintype "passive"))
      (node (ref "J1") (pin "10") (pinfunction "10_10") (pintype "passive"))
      (node (ref "Q12") (pin "2") (pinfunction "SOURCE_2") (pintype "passive"))
      (node (ref "R40") (pin "2") (pinfunction "2_2") (pintype "passive"))
      (node (ref "R44") (pin "2") (pinfunction "2_2") (pintype "passive"))
    )
    (net (code "29") (name "/Cell9") (class "Default")
      (node (ref "C14") (pin "2") (pinfunction "2_2") (pintype "passive"))
      (node (ref "C5") (pin "1") (pinfunction "1_1") (pintype "passive"))
      (node (ref "D3") (pin "2") (pinfunction "K_2") (pintype "passive"))
      (node (ref "J1") (pin "9") (pinfunction "9_9") (pintype "passive"))
      (node (ref "Q8") (pin "2") (pinfunction "SOURCE_2") (pintype "passive"))
      (node (ref "R22") (pin "2") (pinfunction "2_2") (pintype "passive"))
      (node (ref "R27") (pin "2") (pinfunction "2_2") (pintype "passive"))
    )
    (net (code "30") (name "/Cell10") (class "Default")
      (node (ref "C34") (pin "1") (pinfunction "1_1") (pintype "passive"))
      (node (ref "C5") (pin "2") (pinfunction "2_2") (pintype "passive"))
      (node (ref "D18") (pin "2") (pinfunction "K_2") (pintype "passive"))
      (node (ref "J1") (pin "12") (pinfunction "12_12") (pintype "passive"))
      (node (ref "Q3") (pin "2") (pinfunction "SOURCE_2") (pintype "passive"))
      (node (ref "R4") (pin "2") (pinfunction "2_2") (pintype "passive"))
      (node (ref "R73") (pin "2") (pinfunction "2_2") (pintype "passive"))
    )
    (net (code "31") (name "/Cell11") (class "Default")
      (node (ref "D16") (pin "2") (pinfunction "K_2") (pintype "passive"))
      (node (ref "J1") (pin "11") (pinfunction "11_11") (pintype "passive"))
      (node (ref "Q18") (pin "2") (pinfunction "SOURCE_2") (pintype "passive"))
      (node (ref "R65") (pin "2") (pinfunction "2_2") (pintype "passive"))
      (node (ref "R67") (pin "2") (pinfunction "2_2") (pintype "passive"))
    )
    (net (code "32") (name "/Cell12") (class "Default")
      (node (ref "C25") (pin "1") (pinfunction "1_1") (pintype "passive"))
      (node (ref "C30") (pin "2") (pinfunction "2_2") (pintype "passive"))
      (node (ref "D13") (pin "2") (pinfunction "K_2") (pintype "passive"))
      (node (ref "J1") (pin "14") (pinfunction "14_14") (pintype "passive"))
      (node (ref "Q16") (pin "2") (pinfunction "SOURCE_2") (pintype "passive"))
      (node (ref "R56") (pin "2") (pinfunction "2_2") (pintype "passive"))
      (node (ref "R59") (pin "2") (pinfunction "2_2") (pintype "passive"))
    )
    (net (code "33") (name "/Cell13") (class "Default")
      (node (ref "C16") (pin "1") (pinfunction "1_1") (pintype "passive"))
      (node (ref "C25") (pin "2") (pinfunction "2_2") (pintype "passive"))
      (node (ref "D9") (pin "2") (pinfunction "K_2") (pintype "passive"))
      (node (ref "J1") (pin "13") (pinfunction "13_13") (pintype "passive"))
      (node (ref "Q13") (pin "2") (pinfunction "SOURCE_2") (pintype "passive"))
      (node (ref "R41") (pin "2") (pinfunction "2_2") (pintype "passive"))
      (node (ref "R45") (pin "2") (pinfunction "2_2") (pintype "passive"))
    )
    (net (code "34") (name "/Cell14") (class "Default")
      (node (ref "C16") (pin "2") (pinfunction "2_2") (pintype "passive"))
      (node (ref "C6") (pin "1") (pinfunction "1_1") (pintype "passive"))
      (node (ref "D5") (pin "2") (pinfunction "K_2") (pintype "passive"))
      (node (ref "J1") (pin "16") (pinfunction "16_16") (pintype "passive"))
      (node (ref "Q9") (pin "2") (pinfunction "SOURCE_2") (pintype "passive"))
      (node (ref "R24") (pin "2") (pinfunction "2_2") (pintype "passive"))
      (node (ref "R28") (pin "2") (pinfunction "2_2") (pintype "passive"))
    )
    (net (code "35") (name "/Cell15") (class "Default")
      (node (ref "C22") (pin "1") (pinfunction "1_1") (pintype "passive"))
      (node (ref "C6") (pin "2") (pinfunction "2_2") (pintype "passive"))
      (node (ref "D14") (pin "2") (pinfunction "K_2") (pintype "passive"))
      (node (ref "J1") (pin "15") (pinfunction "15_15") (pintype "passive"))
      (node (ref "Q5") (pin "2") (pinfunction "SOURCE_2") (pintype "passive"))
      (node (ref "R57") (pin "2") (pinfunction "2_2") (pintype "passive"))
      (node (ref "R6") (pin "2") (pinfunction "2_2") (pintype "passive"))
    )
    (net (code "36") (name "/Cell16") (class "Default")
      (node (ref "D11") (pin "2") (pinfunction "K_2") (pintype "passive"))
      (node (ref "J1") (pin "18") (pinfunction "18_18") (pintype "passive"))
      (node (ref "Q14") (pin "2") (pinfunction "SOURCE_2") (pintype "passive"))
      (node (ref "R42") (pin "2") (pinfunction "2_2") (pintype "passive"))
      (node (ref "R47") (pin "2") (pinfunction "2_2") (pintype "passive"))
    )
    (net (code "37") (name "/Cell17") (class "Default")
      (node (ref "C13") (pin "2") (pinfunction "2_2") (pintype "passive"))
      (node (ref "C7") (pin "1") (pinfunction "1_1") (pintype "passive"))
      (node (ref "D6") (pin "2") (pinfunction "K_2") (pintype "passive"))
      (node (ref "J1") (pin "17") (pinfunction "17_17") (pintype "passive"))
      (node (ref "Q11") (pin "2") (pinfunction "SOURCE_2") (pintype "passive"))
      (node (ref "R25") (pin "2") (pinfunction "2_2") (pintype "passive"))
      (node (ref "R30") (pin "2") (pinfunction "2_2") (pintype "passive"))
    )
    (net (code "38") (name "/Cell18") (class "Default")
      (node (ref "C7") (pin "2") (pinfunction "2_2") (pintype "passive"))
      (node (ref "J1") (pin "20") (pinfunction "20_20") (pintype "passive"))
      (node (ref "Q6") (pin "2") (pinfunction "SOURCE_2") (pintype "passive"))
      (node (ref "R7") (pin "2") (pinfunction "2_2") (pintype "passive"))
    )
    (net (code "39") (name "/S1") (class "Default")
      (node (ref "R1") (pin "1") (pinfunction "1_1") (pintype "passive"))
    )
    (net (code "40") (name "/S5") (class "Default")
      (node (ref "R9") (pin "1") (pinfunction "1_1") (pintype "passive"))
    )
    (net (code "41") (name "/S6") (class "Default")
      (node (ref "R68") (pin "1") (pinfunction "1_1") (pintype "passive"))
    )
    (net (code "42") (name "/S10") (class "Default")
      (node (ref "R10") (pin "1") (pinfunction "1_1") (pintype "passive"))
    )
    (net (code "43") (name "/S11") (class "Default")
      (node (ref "R69") (pin "1") (pinfunction "1_1") (pintype "passive"))
    )
    (net (code "44") (name "/S15") (class "Default")
      (node (ref "R12") (pin "1") (pinfunction "1_1") (pintype "passive"))
    )
    (net (code "45") (name "/S16") (class "Default")
      (node (ref "R51") (pin "1") (pinfunction "1_1") (pintype "passive"))
    )
    (net (code "46") (name "<NO NET>") (class "Default")
      (node (ref "C0") (pin "1") (pinfunction "1_1") (pintype "passive"))
      (node (ref "C10") (pin "1") (pinfunction "1_1") (pintype "passive"))
      (node (ref "C11") (pin "1") (pinfunction "1_1") (pintype "passive"))
      (node (ref "C12") (pin "1") (pinfunction "1_1") (pintype "passive"))
      (node (ref "C15") (pin "1") (pinfunction "1_1") (pintype "passive"))
      (node (ref "C17") (pin "1") (pinfunction "1_1") (pintype "passive"))
      (node (ref "C18") (pin "1") (pinfunction "1_1") (pintype "passive"))
      (node (ref "C19") (pin "1") (pinfunction "1_1") (pintype "passive"))
      (node (ref "C20") (pin "1") (pinfunction "1_1") (pintype "passive"))
      (node (ref "C21") (pin "1") (pinfunction "1_1") (pintype "passive"))
      (node (ref "C24") (pin "1") (pinfunction "1_1") (pintype "passive"))
      (node (ref "C26") (pin "1") (pinfunction "1_1") (pintype "passive"))
      (node (ref "C27") (pin "1") (pinfunction "1_1") (pintype "passive"))
      (node (ref "C28") (pin "1") (pinfunction "1_1") (pintype "passive"))
      (node (ref "C31") (pin "1") (pinfunction "1_1") (pintype "passive"))
      (node (ref "C32") (pin "1") (pinfunction "1_1") (pintype "passive"))
      (node (ref "C35") (pin "1") (pinfunction "1_1") (pintype "passive"))
      (node (ref "C36") (pin "1") (pinfunction "1_1") (pintype "passive"))
      (node (ref "C8") (pin "1") (pinfunction "1_1") (pintype "passive"))
      (node (ref "C9") (pin "1") (pinfunction "1_1") (pintype "passive"))
      (node (ref "D10") (pin "2") (pinfunction "K_2") (pintype "passive"))
      (node (ref "J1") (pin "19") (pinfunction "19_19") (pintype "passive"))
      (node (ref "R46") (pin "2") (pinfunction "2_2") (pintype "passive"))
      (node (ref "R49") (pin "2") (pinfunction "2_2") (pintype "passive"))
    )
    (net (code "47") (name "Net-(C0-Pad2)") (class "Default")
      (node (ref "C0") (pin "2") (pinfunction "2_2") (pintype "passive"))
      (node (ref "C1") (pin "1") (pinfunction "1_1") (pintype "passive"))
    )
    (net (code "48") (name "Net-(C13-Pad1)") (class "Default")
      (node (ref "C13") (pin "1") (pinfunction "1_1") (pintype "passive"))
      (node (ref "C22") (pin "2") (pinfunction "2_2") (pintype "passive"))
    )
    (net (code "49") (name "Net-(C29-Pad1)") (class "Default")
      (node (ref "C29") (pin "1") (pinfunction "1_1") (pintype "passive"))
      (node (ref "C33") (pin "2") (pinfunction "2_2") (pintype "passive"))
    )
    (net (code "50") (name "Net-(C30-Pad1)") (class "Default")
      (node (ref "C30") (pin "1") (pinfunction "1_1") (pintype "passive"))
      (node (ref "C34") (pin "2") (pinfunction "2_2") (pintype "passive"))
    )
    (net (code "51") (name "Net-(D1-A)") (class "Default")
      (node (ref "D1") (pin "1") (pinfunction "A_1") (pintype "passive"))
      (node (ref "R8") (pin "2") (pinfunction "2_2") (pintype "passive"))
    )
    (net (code "52") (name "Net-(D2-A)") (class "Default")
      (node (ref "D2") (pin "1") (pinfunction "A_1") (pintype "passive"))
      (node (ref "R15") (pin "2") (pinfunction "2_2") (pintype "passive"))
    )
    (net (code "53") (name "Net-(D3-A)") (class "Default")
      (node (ref "D3") (pin "1") (pinfunction "A_1") (pintype "passive"))
      (node (ref "R16") (pin "2") (pinfunction "2_2") (pintype "passive"))
    )
    (net (code "54") (name "Net-(D4-A)") (class "Default")
      (node (ref "D4") (pin "1") (pinfunction "A_1") (pintype "passive"))
      (node (ref "R20") (pin "2") (pinfunction "2_2") (pintype "passive"))
    )
    (net (code "55") (name "Net-(D5-A)") (class "Default")
      (node (ref "D5") (pin "1") (pinfunction "A_1") (pintype "passive"))
      (node (ref "R18") (pin "2") (pinfunction "2_2") (pintype "passive"))
    )
    (net (code "56") (name "Net-(D6-A)") (class "Default")
      (node (ref "D6") (pin "1") (pinfunction "A_1") (pintype "passive"))
      (node (ref "R19") (pin "2") (pinfunction "2_2") (pintype "passive"))
    )
    (net (code "57") (name "Net-(D7-A)") (class "Default")
      (node (ref "D7") (pin "1") (pinfunction "A_1") (pintype "passive"))
      (node (ref "R32") (pin "2") (pinfunction "2_2") (pintype "passive"))
    )
    (net (code "58") (name "Net-(D8-A)") (class "Default")
      (node (ref "D8") (pin "1") (pinfunction "A_1") (pintype "passive"))
      (node (ref "R36") (pin "2") (pinfunction "2_2") (pintype "passive"))
    )
    (net (code "59") (name "Net-(D9-A)") (class "Default")
      (node (ref "D9") (pin "1") (pinfunction "A_1") (pintype "passive"))
      (node (ref "R37") (pin "2") (pinfunction "2_2") (pintype "passive"))
    )
    (net (code "60") (name "Net-(D10-A)") (class "Default")
      (node (ref "D10") (pin "1") (pinfunction "A_1") (pintype "passive"))
      (node (ref "R43") (pin "2") (pinfunction "2_2") (pintype "passive"))
    )
    (net (code "61") (name "Net-(D11-A)") (class "Default")
      (node (ref "D11") (pin "1") (pinfunction "A_1") (pintype "passive"))
      (node (ref "R39") (pin "2") (pinfunction "2_2") (pintype "passive"))
    )
    (net (code "62") (name "Net-(D12-A)") (class "Default")
      (node (ref "D12") (pin "1") (pinfunction "A_1") (pintype "passive"))
      (node (ref "R52") (pin "2") (pinfunction "2_2") (pintype "passive"))
    )
    (net (code "63") (name "Net-(D13-A)") (class "Default")
      (node (ref "D13") (pin "1") (pinfunction "A_1") (pintype "passive"))
      (node (ref "R53") (pin "2") (pinfunction "2_2") (pintype "passive"))
    )
    (net (code "64") (name "Net-(D14-A)") (class "Default")
      (node (ref "D14") (pin "1") (pinfunction "A_1") (pintype "passive"))
      (node (ref "R54") (pin "2") (pinfunction "2_2") (pintype "passive"))
    )
    (net (code "65") (name "Net-(D15-A)") (class "Default")
      (node (ref "D15") (pin "1") (pinfunction "A_1") (pintype "passive"))
      (node (ref "R62") (pin "2") (pinfunction "2_2") (pintype "passive"))
    )
    (net (code "66") (name "Net-(D16-A)") (class "Default")
      (node (ref "D16") (pin "1") (pinfunction "A_1") (pintype "passive"))
      (node (ref "R63") (pin "2") (pinfunction "2_2") (pintype "passive"))
    )
    (net (code "67") (name "Net-(D17-A)") (class "Default")
      (node (ref "D17") (pin "1") (pinfunction "A_1") (pintype "passive"))
      (node (ref "R70") (pin "2") (pinfunction "2_2") (pintype "passive"))
    )
    (net (code "68") (name "Net-(D18-A)") (class "Default")
      (node (ref "D18") (pin "1") (pinfunction "A_1") (pintype "passive"))
      (node (ref "R71") (pin "2") (pinfunction "2_2") (pintype "passive"))
    )
    (net (code "69") (name "Net-(Q1-DRAIN)") (class "Default")
      (node (ref "Q1") (pin "3") (pinfunction "DRAIN_3") (pintype "passive"))
      (node (ref "R11") (pin "1") (pinfunction "1_1") (pintype "passive"))
      (node (ref "R8") (pin "1") (pinfunction "1_1") (pintype "passive"))
    )
    (net (code "70") (name "Net-(Q1-GATE)") (class "Default")
      (node (ref "Q1") (pin "1") (pinfunction "GATE_1") (pintype "passive"))
      (node (ref "R5") (pin "2") (pinfunction "2_2") (pintype "passive"))
    )
    (net (code "71") (name "Net-(Q2-DRAIN)") (class "Default")
      (node (ref "Q2") (pin "3") (pinfunction "DRAIN_3") (pintype "passive"))
      (node (ref "R15") (pin "1") (pinfunction "1_1") (pintype "passive"))
      (node (ref "R21") (pin "1") (pinfunction "1_1") (pintype "passive"))
    )
    (net (code "72") (name "Net-(Q2-GATE)") (class "Default")
      (node (ref "Q2") (pin "1") (pinfunction "GATE_1") (pintype "passive"))
      (node (ref "R9") (pin "2") (pinfunction "2_2") (pintype "passive"))
    )
    (net (code "73") (name "Net-(Q3-DRAIN)") (class "Default")
      (node (ref "Q3") (pin "3") (pinfunction "DRAIN_3") (pintype "passive"))
      (node (ref "R16") (pin "1") (pinfunction "1_1") (pintype "passive"))
      (node (ref "R22") (pin "1") (pinfunction "1_1") (pintype "passive"))
    )
    (net (code "74") (name "Net-(Q3-GATE)") (class "Default")
      (node (ref "Q3") (pin "1") (pinfunction "GATE_1") (pintype "passive"))
      (node (ref "R10") (pin "2") (pinfunction "2_2") (pintype "passive"))
    )
    (net (code "75") (name "Net-(Q4-DRAIN)") (class "Default")
      (node (ref "Q4") (pin "3") (pinfunction "DRAIN_3") (pintype "passive"))
      (node (ref "R20") (pin "1") (pinfunction "1_1") (pintype "passive"))
      (node (ref "R23") (pin "1") (pinfunction "1_1") (pintype "passive"))
    )
    (net (code "76") (name "Net-(Q4-GATE)") (class "Default")
      (node (ref "Q4") (pin "1") (pinfunction "GATE_1") (pintype "passive"))
      (node (ref "R17") (pin "2") (pinfunction "2_2") (pintype "passive"))
    )
    (net (code "77") (name "Net-(Q5-DRAIN)") (class "Default")
      (node (ref "Q5") (pin "3") (pinfunction "DRAIN_3") (pintype "passive"))
      (node (ref "R18") (pin "1") (pinfunction "1_1") (pintype "passive"))
      (node (ref "R24") (pin "1") (pinfunction "1_1") (pintype "passive"))
    )
    (net (code "78") (name "Net-(Q5-GATE)") (class "Default")
      (node (ref "Q5") (pin "1") (pinfunction "GATE_1") (pintype "passive"))
      (node (ref "R12") (pin "2") (pinfunction "2_2") (pintype "passive"))
    )
    (net (code "79") (name "Net-(Q6-DRAIN)") (class "Default")
      (node (ref "Q6") (pin "3") (pinfunction "DRAIN_3") (pintype "passive"))
      (node (ref "R19") (pin "1") (pinfunction "1_1") (pintype "passive"))
      (node (ref "R25") (pin "1") (pinfunction "1_1") (pintype "passive"))
    )
    (net (code "80") (name "Net-(Q6-GATE)") (class "Default")
      (node (ref "Q6") (pin "1") (pinfunction "GATE_1") (pintype "passive"))
      (node (ref "R13") (pin "2") (pinfunction "2_2") (pintype "passive"))
    )
    (net (code "81") (name "Net-(Q7-DRAIN)") (class "Default")
      (node (ref "Q7") (pin "3") (pinfunction "DRAIN_3") (pintype "passive"))
      (node (ref "R32") (pin "1") (pinfunction "1_1") (pintype "passive"))
      (node (ref "R35") (pin "1") (pinfunction "1_1") (pintype "passive"))
    )
    (net (code "82") (name "Net-(Q7-GATE)") (class "Default")
      (node (ref "Q7") (pin "1") (pinfunction "GATE_1") (pintype "passive"))
      (node (ref "R29") (pin "2") (pinfunction "2_2") (pintype "passive"))
    )
    (net (code "83") (name "Net-(Q8-DRAIN)") (class "Default")
      (node (ref "Q8") (pin "3") (pinfunction "DRAIN_3") (pintype "passive"))
      (node (ref "R36") (pin "1") (pinfunction "1_1") (pintype "passive"))
      (node (ref "R40") (pin "1") (pinfunction "1_1") (pintype "passive"))
    )
    (net (code "84") (name "Net-(Q8-GATE)") (class "Default")
      (node (ref "Q8") (pin "1") (pinfunction "GATE_1") (pintype "passive"))
      (node (ref "R31") (pin "2") (pinfunction "2_2") (pintype "passive"))
    )
    (net (code "85") (name "Net-(Q9-DRAIN)") (class "Default")
      (node (ref "Q9") (pin "3") (pinfunction "DRAIN_3") (pintype "passive"))
      (node (ref "R37") (pin "1") (pinfunction "1_1") (pintype "passive"))
      (node (ref "R41") (pin "1") (pinfunction "1_1") (pintype "passive"))
    )
    (net (code "86") (name "Net-(Q9-GATE)") (class "Default")
      (node (ref "Q9") (pin "1") (pinfunction "GATE_1") (pintype "passive"))
      (node (ref "R33") (pin "2") (pinfunction "2_2") (pintype "passive"))
    )
    (net (code "87") (name "Net-(Q10-DRAIN)") (class "Default")
      (node (ref "Q10") (pin "3") (pinfunction "DRAIN_3") (pintype "passive"))
      (node (ref "R43") (pin "1") (pinfunction "1_1") (pintype "passive"))
      (node (ref "R46") (pin "1") (pinfunction "1_1") (pintype "passive"))
    )
    (net (code "88") (name "Net-(Q10-GATE)") (class "Default")
      (node (ref "Q10") (pin "1") (pinfunction "GATE_1") (pintype "passive"))
      (node (ref "R1") (pin "2") (pinfunction "2_2") (pintype "passive"))
    )
    (net (code "89") (name "Net-(Q11-DRAIN)") (class "Default")
      (node (ref "Q11") (pin "3") (pinfunction "DRAIN_3") (pintype "passive"))
      (node (ref "R39") (pin "1") (pinfunction "1_1") (pintype "passive"))
      (node (ref "R42") (pin "1") (pinfunction "1_1") (pintype "passive"))
    )
    (net (code "90") (name "Net-(Q11-GATE)") (class "Default")
      (node (ref "Q11") (pin "1") (pinfunction "GATE_1") (pintype "passive"))
      (node (ref "R34") (pin "2") (pinfunction "2_2") (pintype "passive"))
    )
    (net (code "91") (name "Net-(Q12-DRAIN)") (class "Default")
      (node (ref "Q12") (pin "3") (pinfunction "DRAIN_3") (pintype "passive"))
      (node (ref "R52") (pin "1") (pinfunction "1_1") (pintype "passive"))
      (node (ref "R55") (pin "1") (pinfunction "1_1") (pintype "passive"))
    )
    (net (code "92") (name "Net-(Q12-GATE)") (class "Default")
      (node (ref "Q12") (pin "1") (pinfunction "GATE_1") (pintype "passive"))
      (node (ref "R48") (pin "2") (pinfunction "2_2") (pintype "passive"))
    )
    (net (code "93") (name "Net-(Q13-DRAIN)") (class "Default")
      (node (ref "Q13") (pin "3") (pinfunction "DRAIN_3") (pintype "passive"))
      (node (ref "R53") (pin "1") (pinfunction "1_1") (pintype "passive"))
      (node (ref "R56") (pin "1") (pinfunction "1_1") (pintype "passive"))
    )
    (net (code "94") (name "Net-(Q13-GATE)") (class "Default")
      (node (ref "Q13") (pin "1") (pinfunction "GATE_1") (pintype "passive"))
      (node (ref "R50") (pin "2") (pinfunction "2_2") (pintype "passive"))
    )
    (net (code "95") (name "Net-(Q14-DRAIN)") (class "Default")
      (node (ref "Q14") (pin "3") (pinfunction "DRAIN_3") (pintype "passive"))
      (node (ref "R54") (pin "1") (pinfunction "1_1") (pintype "passive"))
      (node (ref "R57") (pin "1") (pinfunction "1_1") (pintype "passive"))
    )
    (net (code "96") (name "Net-(Q14-GATE)") (class "Default")
      (node (ref "Q14") (pin "1") (pinfunction "GATE_1") (pintype "passive"))
      (node (ref "R51") (pin "2") (pinfunction "2_2") (pintype "passive"))
    )
    (net (code "97") (name "Net-(Q15-DRAIN)") (class "Default")
      (node (ref "Q15") (pin "3") (pinfunction "DRAIN_3") (pintype "passive"))
      (node (ref "R62") (pin "1") (pinfunction "1_1") (pintype "passive"))
      (node (ref "R64") (pin "1") (pinfunction "1_1") (pintype "passive"))
    )
    (net (code "98") (name "Net-(Q15-GATE)") (class "Default")
      (node (ref "Q15") (pin "1") (pinfunction "GATE_1") (pintype "passive"))
      (node (ref "R60") (pin "2") (pinfunction "2_2") (pintype "passive"))
    )
    (net (code "99") (name "Net-(Q16-DRAIN)") (class "Default")
      (node (ref "Q16") (pin "3") (pinfunction "DRAIN_3") (pintype "passive"))
      (node (ref "R63") (pin "1") (pinfunction "1_1") (pintype "passive"))
      (node (ref "R65") (pin "1") (pinfunction "1_1") (pintype "passive"))
    )
    (net (code "100") (name "Net-(Q16-GATE)") (class "Default")
      (node (ref "Q16") (pin "1") (pinfunction "GATE_1") (pintype "passive"))
      (node (ref "R61") (pin "2") (pinfunction "2_2") (pintype "passive"))
    )
    (net (code "101") (name "Net-(Q17-DRAIN)") (class "Default")
      (node (ref "Q17") (pin "3") (pinfunction "DRAIN_3") (pintype "passive"))
      (node (ref "R70") (pin "1") (pinfunction "1_1") (pintype "passive"))
      (node (ref "R72") (pin "1") (pinfunction "1_1") (pintype "passive"))
    )
    (net (code "102") (name "Net-(Q17-GATE)") (class "Default")
      (node (ref "Q17") (pin "1") (pinfunction "GATE_1") (pintype "passive"))
      (node (ref "R68") (pin "2") (pinfunction "2_2") (pintype "passive"))
    )
    (net (code "103") (name "Net-(Q18-DRAIN)") (class "Default")
      (node (ref "Q18") (pin "3") (pinfunction "DRAIN_3") (pintype "passive"))
      (node (ref "R71") (pin "1") (pinfunction "1_1") (pintype "passive"))
      (node (ref "R73") (pin "1") (pinfunction "1_1") (pintype "passive"))
    )
    (net (code "104") (name "Net-(Q18-GATE)") (class "Default")
      (node (ref "Q18") (pin "1") (pinfunction "GATE_1") (pintype "passive"))
      (node (ref "R69") (pin "2") (pinfunction "2_2") (pintype "passive"))
    )
    (net (code "105") (name "unconnected-(J1A-MNT_1-Pad21)") (class "Default")
      (node (ref "J1") (pin "21") (pinfunction "MNT_1_21") (pintype "passive"))
    )
    (net (code "106") (name "unconnected-(J1B-MNT_2-Pad22)") (class "Default")
      (node (ref "J1") (pin "22") (pinfunction "MNT_2_22") (pintype "passive"))
    )
  )
)
